# rgb_driver_double_layer.net
KiCad netlist of a schematic drawn in EAGLE
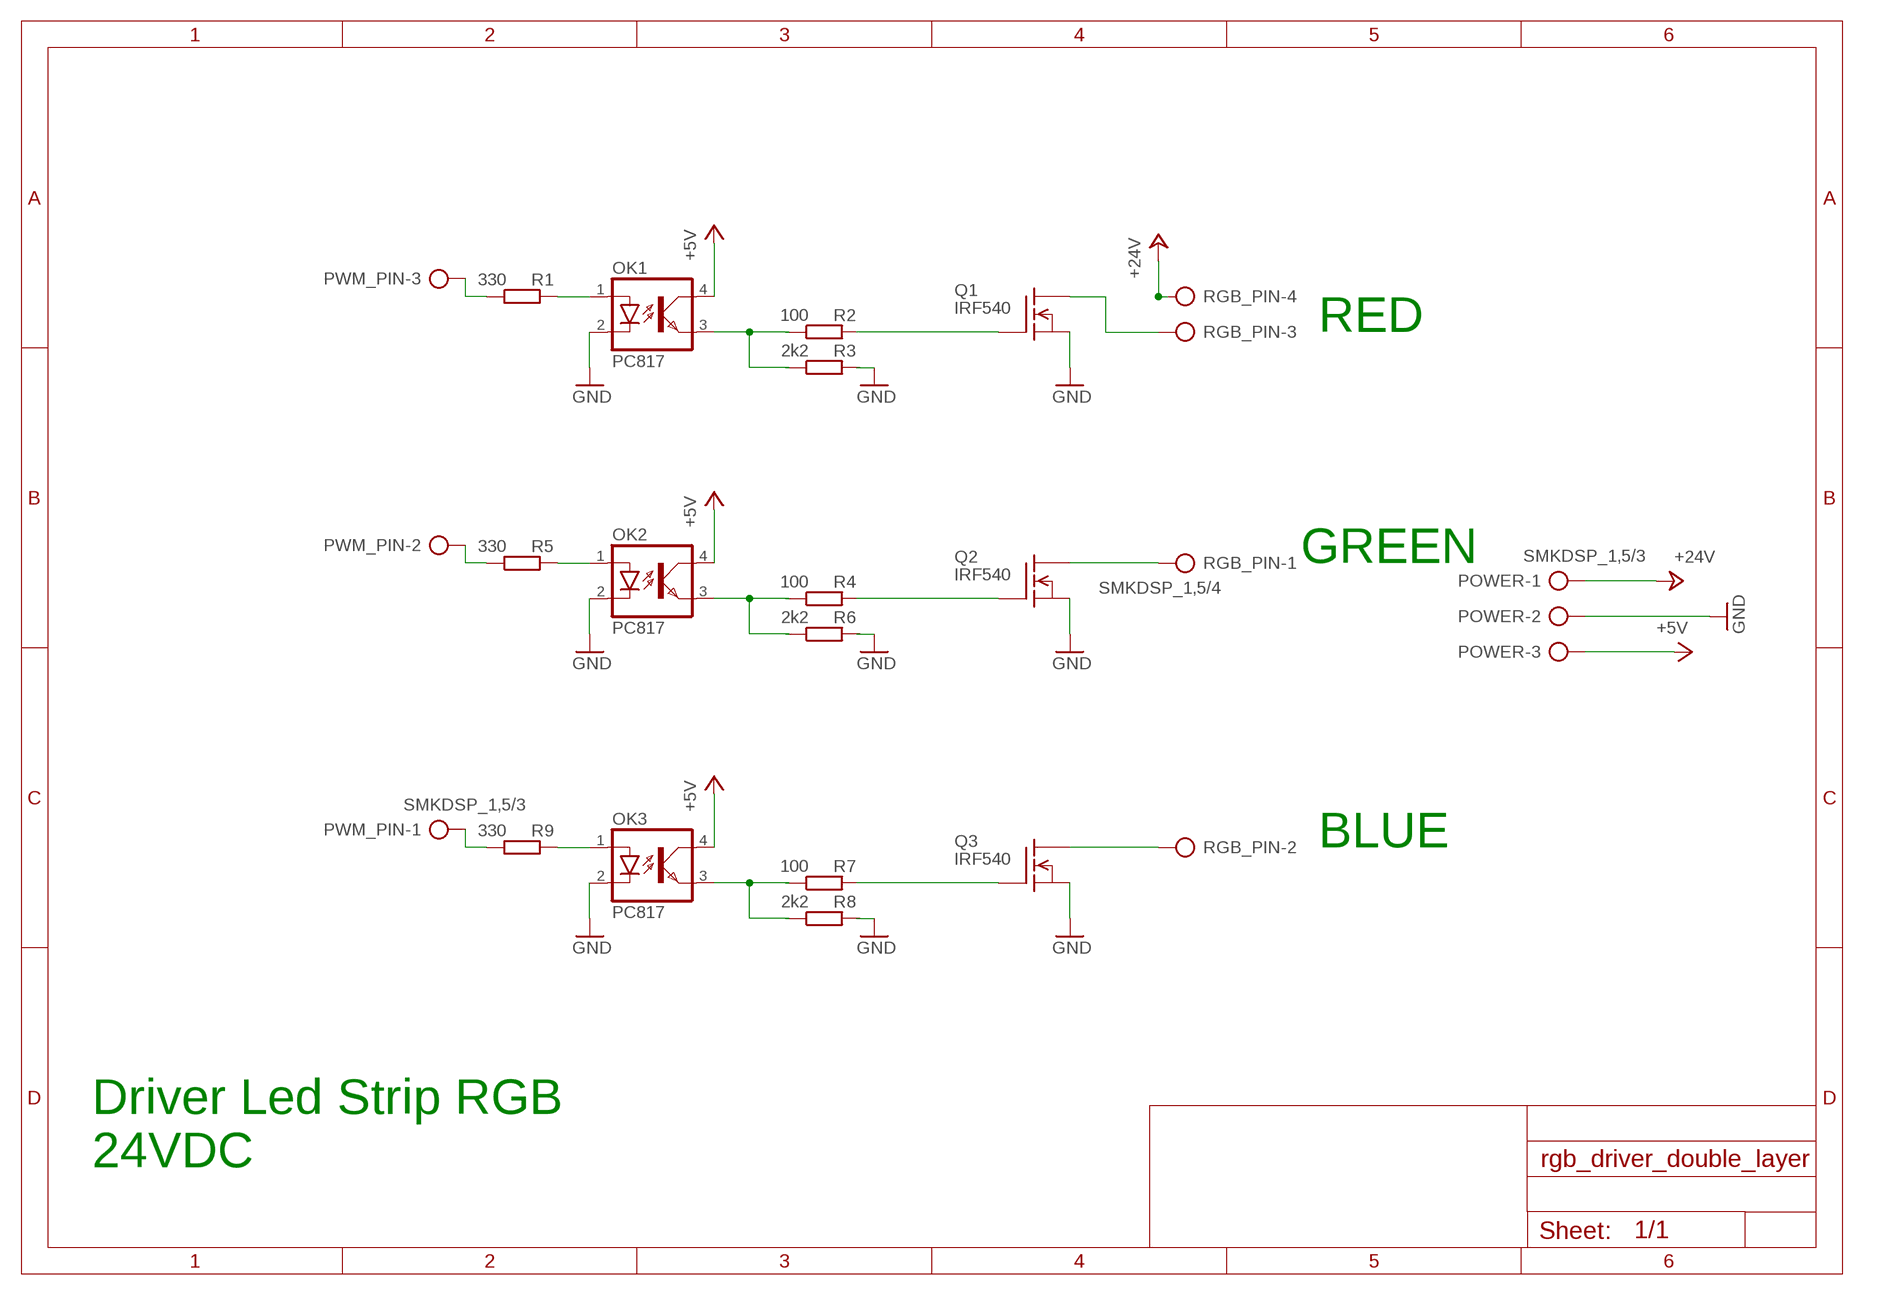
[diagram p0: schematic, sheet 1]

(export (version "E")
  (design (tool "Eeschema 10.0.6"))
  (components
    (comp (ref "OK1")
      (value "PC817")
      (footprint "eagle-import:DIL04")
      (fields (field (name "MPN") "PC817X4J000F"))
      (libsource (lib "eagle-import") (part "PC817"))
    )
    (comp (ref "OK2")
      (value "PC817")
      (footprint "eagle-import:DIL04")
      (fields (field (name "MPN") "PC817X4J000F"))
      (libsource (lib "eagle-import") (part "PC817"))
    )
    (comp (ref "OK3")
      (value "PC817")
      (footprint "eagle-import:DIL04")
      (fields (field (name "MPN") "PC817X4J000F"))
      (libsource (lib "eagle-import") (part "PC817"))
    )
    (comp (ref "POWER")
      (value "SMKDSP_1,5/3")
      (footprint "eagle-import:SMKDSP_1,5_3")
      (fields (field (name "MF") "FARNELL") (field (name "MPN") "1733583"))
      (libsource (lib "eagle-import") (part "SMKDSP_1,5/3"))
    )
    (comp (ref "PWM_PIN")
      (value "SMKDSP_1,5/3")
      (footprint "eagle-import:SMKDSP_1,5_3")
      (fields (field (name "MF") "FARNELL") (field (name "MPN") "1733583"))
      (libsource (lib "eagle-import") (part "SMKDSP_1,5/3"))
    )
    (comp (ref "Q1")
      (value "IRF540")
      (footprint "eagle-import:TO220")
      (libsource (lib "eagle-import") (part "IRF540"))
    )
    (comp (ref "Q2")
      (value "IRF540")
      (footprint "eagle-import:TO220")
      (libsource (lib "eagle-import") (part "IRF540"))
    )
    (comp (ref "Q3")
      (value "IRF540")
      (footprint "eagle-import:TO220")
      (libsource (lib "eagle-import") (part "IRF540"))
    )
    (comp (ref "R1")
      (value "330")
      (footprint "eagle-import:0207_10")
      (libsource (lib "eagle-import") (part "R-EU_0207/10"))
    )
    (comp (ref "R2")
      (value "100")
      (footprint "eagle-import:0207_10")
      (libsource (lib "eagle-import") (part "R-EU_0207/10"))
    )
    (comp (ref "R3")
      (value "2k2")
      (footprint "eagle-import:0207_10")
      (libsource (lib "eagle-import") (part "R-EU_0207/10"))
    )
    (comp (ref "R4")
      (value "100")
      (footprint "eagle-import:0207_10")
      (libsource (lib "eagle-import") (part "R-EU_0207/10"))
    )
    (comp (ref "R5")
      (value "330")
      (footprint "eagle-import:0207_10")
      (libsource (lib "eagle-import") (part "R-EU_0207/10"))
    )
    (comp (ref "R6")
      (value "2k2")
      (footprint "eagle-import:0207_10")
      (libsource (lib "eagle-import") (part "R-EU_0207/10"))
    )
    (comp (ref "R7")
      (value "100")
      (footprint "eagle-import:0207_10")
      (libsource (lib "eagle-import") (part "R-EU_0207/10"))
    )
    (comp (ref "R8")
      (value "2k2")
      (footprint "eagle-import:0207_10")
      (libsource (lib "eagle-import") (part "R-EU_0207/10"))
    )
    (comp (ref "R9")
      (value "330")
      (footprint "eagle-import:0207_10")
      (libsource (lib "eagle-import") (part "R-EU_0207/10"))
    )
    (comp (ref "RGB_PIN")
      (value "SMKDSP_1,5/4")
      (footprint "eagle-import:SMKDSP_1,5_4")
      (fields (field (name "MF") "FARNELL") (field (name "MPN") "1733596"))
      (libsource (lib "eagle-import") (part "SMKDSP_1,5/4"))
    )
  )
  (nets
    (net (code "1") (name "+5V") (class "Default")
      (node (ref "OK1") (pin "4") (pinfunction "COL_4") (pintype "passive"))
      (node (ref "OK2") (pin "4") (pinfunction "COL_4") (pintype "passive"))
      (node (ref "OK3") (pin "4") (pinfunction "COL_4") (pintype "passive"))
      (node (ref "POWER") (pin "3") (pinfunction "KL_3") (pintype "passive"))
    )
    (net (code "2") (name "+24V") (class "Default")
      (node (ref "POWER") (pin "1") (pinfunction "KL_1") (pintype "passive"))
      (node (ref "RGB_PIN") (pin "4") (pinfunction "KL_4") (pintype "passive"))
    )
    (net (code "3") (name "GND") (class "Default")
      (node (ref "OK1") (pin "2") (pinfunction "C_2") (pintype "passive"))
      (node (ref "OK2") (pin "2") (pinfunction "C_2") (pintype "passive"))
      (node (ref "OK3") (pin "2") (pinfunction "C_2") (pintype "passive"))
      (node (ref "POWER") (pin "2") (pinfunction "KL_2") (pintype "passive"))
      (node (ref "Q1") (pin "3") (pinfunction "S_3") (pintype "passive"))
      (node (ref "Q2") (pin "3") (pinfunction "S_3") (pintype "passive"))
      (node (ref "Q3") (pin "3") (pinfunction "S_3") (pintype "passive"))
      (node (ref "R3") (pin "2") (pinfunction "2_2") (pintype "passive"))
      (node (ref "R6") (pin "2") (pinfunction "2_2") (pintype "passive"))
      (node (ref "R8") (pin "2") (pinfunction "2_2") (pintype "passive"))
    )
    (net (code "4") (name "Net-(OK1-A)") (class "Default")
      (node (ref "OK1") (pin "1") (pinfunction "A_1") (pintype "passive"))
      (node (ref "R1") (pin "2") (pinfunction "2_2") (pintype "passive"))
    )
    (net (code "5") (name "Net-(OK1-EMIT)") (class "Default")
      (node (ref "OK1") (pin "3") (pinfunction "EMIT_3") (pintype "passive"))
      (node (ref "R2") (pin "1") (pinfunction "1_1") (pintype "passive"))
      (node (ref "R3") (pin "1") (pinfunction "1_1") (pintype "passive"))
    )
    (net (code "6") (name "Net-(OK2-A)") (class "Default")
      (node (ref "OK2") (pin "1") (pinfunction "A_1") (pintype "passive"))
      (node (ref "R5") (pin "2") (pinfunction "2_2") (pintype "passive"))
    )
    (net (code "7") (name "Net-(OK2-EMIT)") (class "Default")
      (node (ref "OK2") (pin "3") (pinfunction "EMIT_3") (pintype "passive"))
      (node (ref "R4") (pin "1") (pinfunction "1_1") (pintype "passive"))
      (node (ref "R6") (pin "1") (pinfunction "1_1") (pintype "passive"))
    )
    (net (code "8") (name "Net-(OK3-A)") (class "Default")
      (node (ref "OK3") (pin "1") (pinfunction "A_1") (pintype "passive"))
      (node (ref "R9") (pin "2") (pinfunction "2_2") (pintype "passive"))
    )
    (net (code "9") (name "Net-(OK3-EMIT)") (class "Default")
      (node (ref "OK3") (pin "3") (pinfunction "EMIT_3") (pintype "passive"))
      (node (ref "R7") (pin "1") (pinfunction "1_1") (pintype "passive"))
      (node (ref "R8") (pin "1") (pinfunction "1_1") (pintype "passive"))
    )
    (net (code "10") (name "Net-(PWM_PINA-KL)") (class "Default")
      (node (ref "PWM_PIN") (pin "1") (pinfunction "KL_1") (pintype "passive"))
      (node (ref "R9") (pin "1") (pinfunction "1_1") (pintype "passive"))
    )
    (net (code "11") (name "Net-(PWM_PINB-KL)") (class "Default")
      (node (ref "PWM_PIN") (pin "2") (pinfunction "KL_2") (pintype "passive"))
      (node (ref "R5") (pin "1") (pinfunction "1_1") (pintype "passive"))
    )
    (net (code "12") (name "Net-(PWM_PINC-KL)") (class "Default")
      (node (ref "PWM_PIN") (pin "3") (pinfunction "KL_3") (pintype "passive"))
      (node (ref "R1") (pin "1") (pinfunction "1_1") (pintype "passive"))
    )
    (net (code "13") (name "Net-(Q1-D)") (class "Default")
      (node (ref "Q1") (pin "2") (pinfunction "D_2") (pintype "passive"))
      (node (ref "RGB_PIN") (pin "3") (pinfunction "KL_3") (pintype "passive"))
    )
    (net (code "14") (name "Net-(Q1-G)") (class "Default")
      (node (ref "Q1") (pin "1") (pinfunction "G_1") (pintype "passive"))
      (node (ref "R2") (pin "2") (pinfunction "2_2") (pintype "passive"))
    )
    (net (code "15") (name "Net-(Q2-D)") (class "Default")
      (node (ref "Q2") (pin "2") (pinfunction "D_2") (pintype "passive"))
      (node (ref "RGB_PIN") (pin "1") (pinfunction "KL_1") (pintype "passive"))
    )
    (net (code "16") (name "Net-(Q2-G)") (class "Default")
      (node (ref "Q2") (pin "1") (pinfunction "G_1") (pintype "passive"))
      (node (ref "R4") (pin "2") (pinfunction "2_2") (pintype "passive"))
    )
    (net (code "17") (name "Net-(Q3-D)") (class "Default")
      (node (ref "Q3") (pin "2") (pinfunction "D_2") (pintype "passive"))
      (node (ref "RGB_PIN") (pin "2") (pinfunction "KL_2") (pintype "passive"))
    )
    (net (code "18") (name "Net-(Q3-G)") (class "Default")
      (node (ref "Q3") (pin "1") (pinfunction "G_1") (pintype "passive"))
      (node (ref "R7") (pin "2") (pinfunction "2_2") (pintype "passive"))
    )
  )
)
